# RC_Engine_Sound_ESP32_B.net
KiCad netlist of a schematic drawn in EAGLE
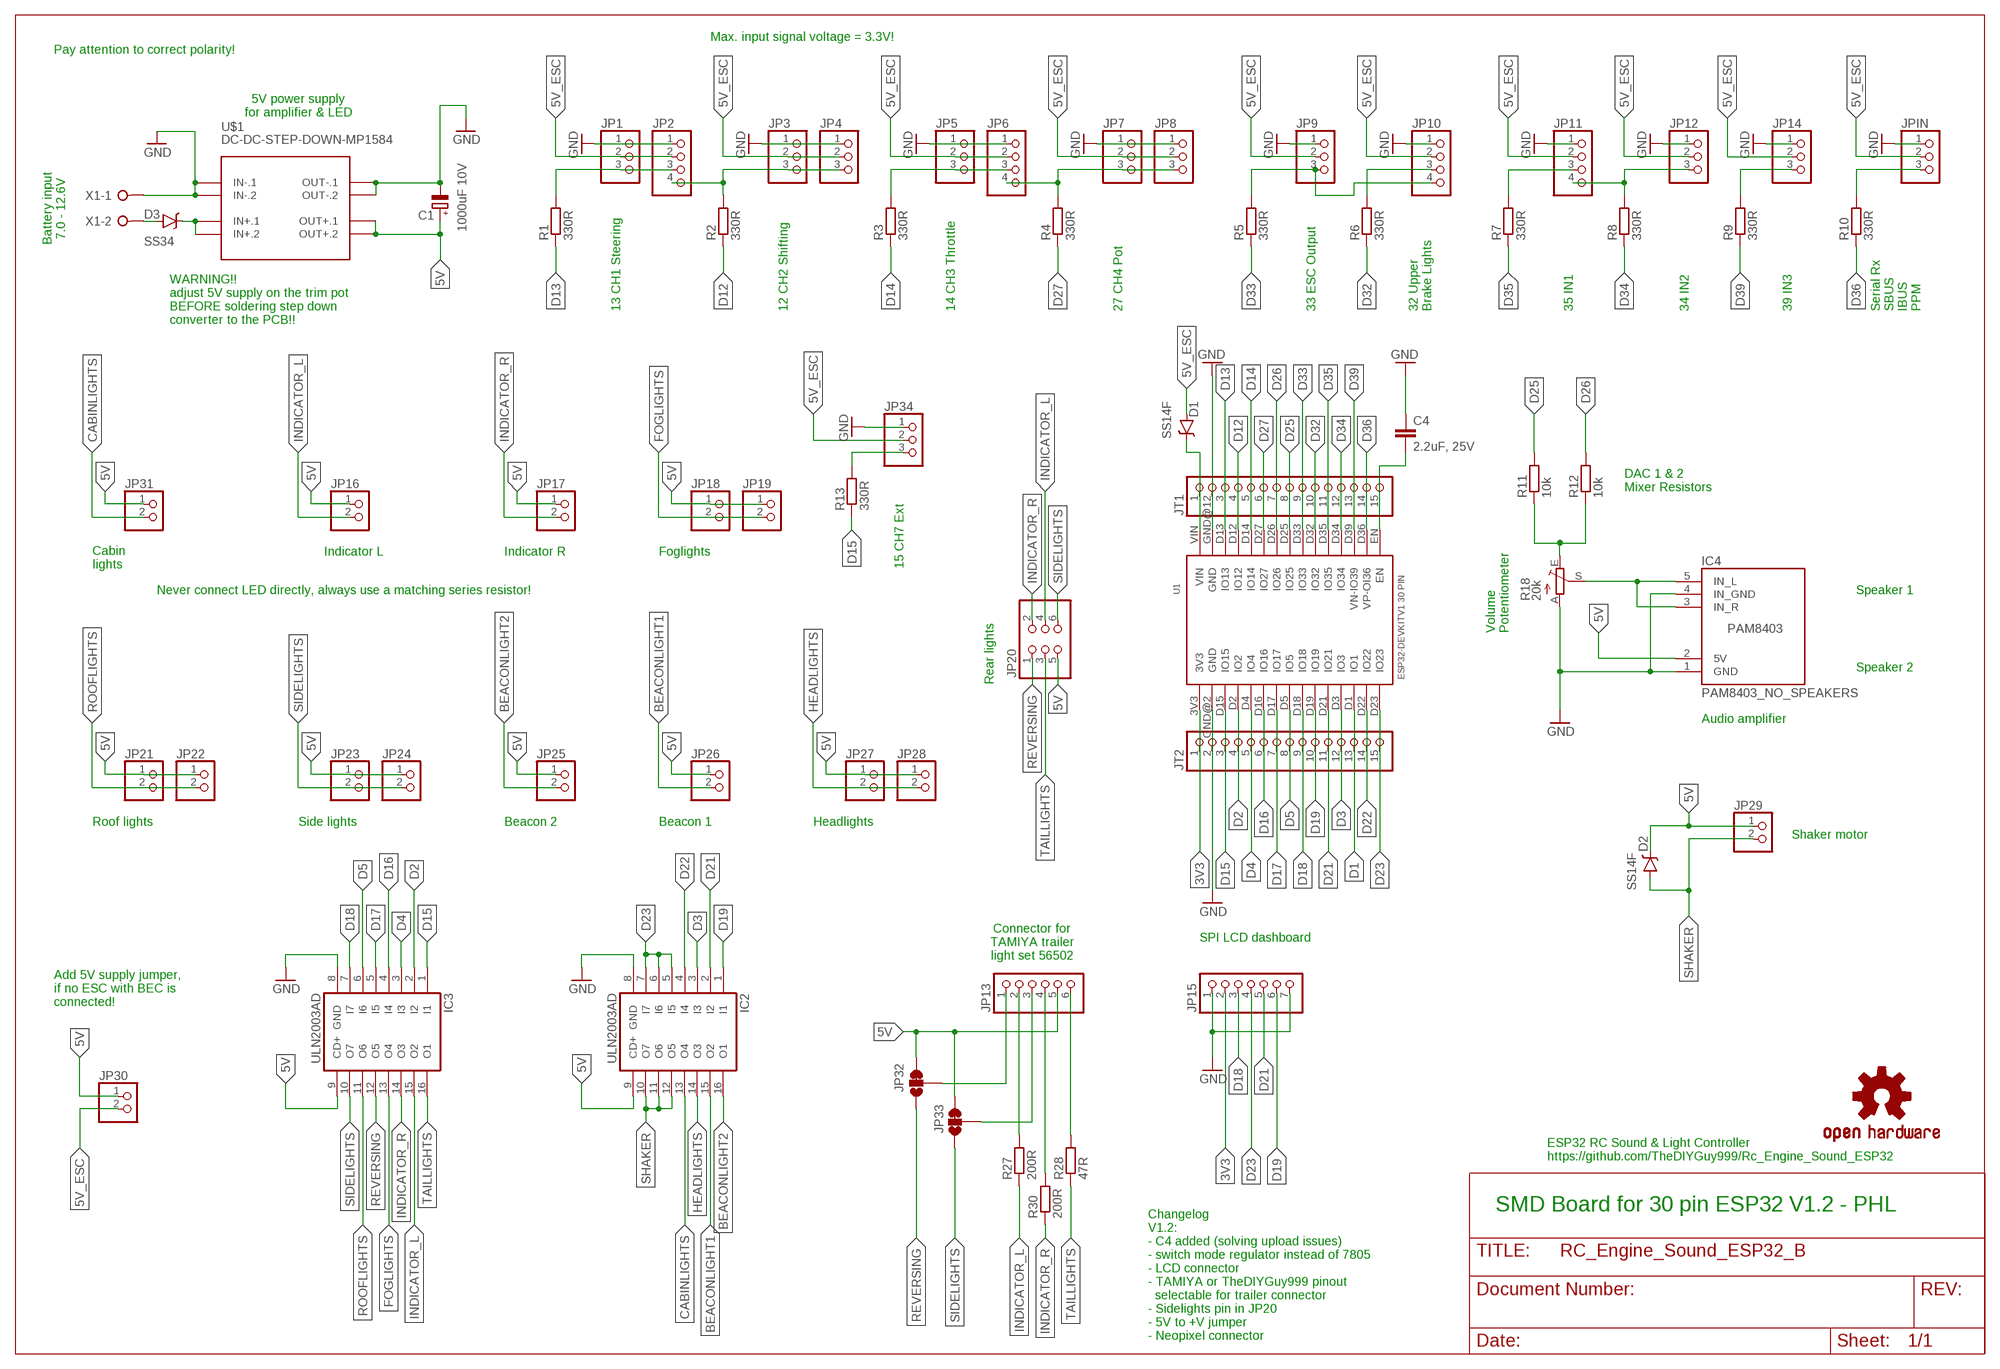
[diagram p0: schematic, sheet 1]

(export (version "E")
  (design (tool "Eeschema 10.0.6"))
  (components
    (comp (ref "C1")
      (value "1000uF 10V")
      (footprint "eagle-import:UD-10X10_NICHICON")
      (libsource (lib "eagle-import") (part "CPOL-EUUD-10X10"))
    )
    (comp (ref "C4")
      (value "2.2uF, 25V")
      (footprint "eagle-import:C1206")
      (libsource (lib "eagle-import") (part "C-EUC1206"))
    )
    (comp (ref "D1")
      (value "SS14F")
      (footprint "eagle-import:SMA-DIODE")
      (libsource (lib "eagle-import") (part "MBRA140"))
    )
    (comp (ref "D2")
      (value "SS14F")
      (footprint "eagle-import:SMA-DIODE")
      (libsource (lib "eagle-import") (part "MBRA140"))
    )
    (comp (ref "D3")
      (value "SS34")
      (footprint "eagle-import:SMA-DIODE")
      (libsource (lib "eagle-import") (part "MBRA140"))
    )
    (comp (ref "IC2")
      (value "ULN2003AD")
      (footprint "eagle-import:SO16")
      (libsource (lib "eagle-import") (part "ULN2003AD"))
    )
    (comp (ref "IC3")
      (value "ULN2003AD")
      (footprint "eagle-import:SO16")
      (libsource (lib "eagle-import") (part "ULN2003AD"))
    )
    (comp (ref "IC4")
      (value "PAM8403_NO_SPEAKERS")
      (footprint "eagle-import:PAM8403_NO_SPEAKERS")
      (libsource (lib "eagle-import") (part "PAM8403_NO_SPEAKERS"))
    )
    (comp (ref "JP1")
      (value "PINHD-1X3")
      (footprint "eagle-import:1X03")
      (libsource (lib "eagle-import") (part "PINHD-1X3"))
    )
    (comp (ref "JP2")
      (value "00_CUSTOM_PINHEAD_PINHD-1X4")
      (footprint "eagle-import:00_CUSTOM_PINHEAD_1X04")
      (libsource (lib "eagle-import") (part "00_CUSTOM_PINHEAD_PINHD-1X4"))
    )
    (comp (ref "JP3")
      (value "PINHD-1X3")
      (footprint "eagle-import:1X03")
      (libsource (lib "eagle-import") (part "PINHD-1X3"))
    )
    (comp (ref "JP4")
      (value "PINHD-1X3")
      (footprint "eagle-import:1X03")
      (libsource (lib "eagle-import") (part "PINHD-1X3"))
    )
    (comp (ref "JP5")
      (value "PINHD-1X3")
      (footprint "eagle-import:1X03")
      (libsource (lib "eagle-import") (part "PINHD-1X3"))
    )
    (comp (ref "JP6")
      (value "00_CUSTOM_PINHEAD_PINHD-1X4")
      (footprint "eagle-import:00_CUSTOM_PINHEAD_1X04")
      (libsource (lib "eagle-import") (part "00_CUSTOM_PINHEAD_PINHD-1X4"))
    )
    (comp (ref "JP7")
      (value "PINHD-1X3")
      (footprint "eagle-import:1X03")
      (libsource (lib "eagle-import") (part "PINHD-1X3"))
    )
    (comp (ref "JP8")
      (value "PINHD-1X3")
      (footprint "eagle-import:1X03")
      (libsource (lib "eagle-import") (part "PINHD-1X3"))
    )
    (comp (ref "JP9")
      (value "PINHD-1X3")
      (footprint "eagle-import:1X03")
      (libsource (lib "eagle-import") (part "PINHD-1X3"))
    )
    (comp (ref "JP10")
      (value "00_CUSTOM_PINHEAD_PINHD-1X4")
      (footprint "eagle-import:00_CUSTOM_PINHEAD_1X04")
      (libsource (lib "eagle-import") (part "00_CUSTOM_PINHEAD_PINHD-1X4"))
    )
    (comp (ref "JP11")
      (value "00_CUSTOM_PINHEAD_PINHD-1X4")
      (footprint "eagle-import:00_CUSTOM_PINHEAD_1X04")
      (libsource (lib "eagle-import") (part "00_CUSTOM_PINHEAD_PINHD-1X4"))
    )
    (comp (ref "JP12")
      (value "PINHD-1X3")
      (footprint "eagle-import:1X03")
      (libsource (lib "eagle-import") (part "PINHD-1X3"))
    )
    (comp (ref "JP13")
      (value "PINHD-1X6")
      (footprint "eagle-import:1X06")
      (libsource (lib "eagle-import") (part "PINHD-1X6"))
    )
    (comp (ref "JP14")
      (value "PINHD-1X3")
      (footprint "eagle-import:1X03")
      (libsource (lib "eagle-import") (part "PINHD-1X3"))
    )
    (comp (ref "JP15")
      (value "PINHD-1X7")
      (footprint "eagle-import:1X07")
      (libsource (lib "eagle-import") (part "PINHD-1X7"))
    )
    (comp (ref "JP16")
      (value "PINHD-1X2")
      (footprint "eagle-import:1X02")
      (libsource (lib "eagle-import") (part "PINHD-1X2"))
    )
    (comp (ref "JP17")
      (value "PINHD-1X2")
      (footprint "eagle-import:1X02")
      (libsource (lib "eagle-import") (part "PINHD-1X2"))
    )
    (comp (ref "JP18")
      (value "PINHD-1X2")
      (footprint "eagle-import:1X02")
      (libsource (lib "eagle-import") (part "PINHD-1X2"))
    )
    (comp (ref "JP19")
      (value "PINHD-1X2")
      (footprint "eagle-import:1X02")
      (libsource (lib "eagle-import") (part "PINHD-1X2"))
    )
    (comp (ref "JP20")
      (value "PINHD-2X3")
      (footprint "eagle-import:2X03")
      (libsource (lib "eagle-import") (part "PINHD-2X3"))
    )
    (comp (ref "JP21")
      (value "PINHD-1X2")
      (footprint "eagle-import:1X02")
      (libsource (lib "eagle-import") (part "PINHD-1X2"))
    )
    (comp (ref "JP22")
      (value "PINHD-1X2")
      (footprint "eagle-import:1X02")
      (libsource (lib "eagle-import") (part "PINHD-1X2"))
    )
    (comp (ref "JP23")
      (value "PINHD-1X2")
      (footprint "eagle-import:1X02")
      (libsource (lib "eagle-import") (part "PINHD-1X2"))
    )
    (comp (ref "JP24")
      (value "PINHD-1X2")
      (footprint "eagle-import:1X02")
      (libsource (lib "eagle-import") (part "PINHD-1X2"))
    )
    (comp (ref "JP25")
      (value "PINHD-1X2")
      (footprint "eagle-import:1X02")
      (libsource (lib "eagle-import") (part "PINHD-1X2"))
    )
    (comp (ref "JP26")
      (value "PINHD-1X2")
      (footprint "eagle-import:1X02")
      (libsource (lib "eagle-import") (part "PINHD-1X2"))
    )
    (comp (ref "JP27")
      (value "PINHD-1X2")
      (footprint "eagle-import:1X02")
      (libsource (lib "eagle-import") (part "PINHD-1X2"))
    )
    (comp (ref "JP28")
      (value "PINHD-1X2")
      (footprint "eagle-import:1X02")
      (libsource (lib "eagle-import") (part "PINHD-1X2"))
    )
    (comp (ref "JP29")
      (value "PINHD-1X2")
      (footprint "eagle-import:1X02")
      (libsource (lib "eagle-import") (part "PINHD-1X2"))
    )
    (comp (ref "JP30")
      (value "PINHD-1X2")
      (footprint "eagle-import:1X02")
      (libsource (lib "eagle-import") (part "PINHD-1X2"))
    )
    (comp (ref "JP31")
      (value "PINHD-1X2")
      (footprint "eagle-import:1X02")
      (libsource (lib "eagle-import") (part "PINHD-1X2"))
    )
    (comp (ref "JP32")
      (value "JUMPER-PAD-3-2OF3_NC_BY_TRACE_LARGE")
      (footprint "eagle-import:PAD-JUMPER-3-2OF3_NC_BY_TRACE_YES_SILK_LARGE")
      (libsource (lib "eagle-import") (part "JUMPER-PAD-3-2OF3_NC_BY_TRACE_LARGE"))
    )
    (comp (ref "JP33")
      (value "JUMPER-PAD-3-2OF3_NC_BY_TRACE_LARGE")
      (footprint "eagle-import:PAD-JUMPER-3-2OF3_NC_BY_TRACE_YES_SILK_LARGE")
      (libsource (lib "eagle-import") (part "JUMPER-PAD-3-2OF3_NC_BY_TRACE_LARGE"))
    )
    (comp (ref "JP34")
      (value "PINHD-1X3")
      (footprint "eagle-import:1X03")
      (libsource (lib "eagle-import") (part "PINHD-1X3"))
    )
    (comp (ref "JPIN")
      (value "PINHD-1X3")
      (footprint "eagle-import:1X03")
      (libsource (lib "eagle-import") (part "PINHD-1X3"))
    )
    (comp (ref "JT1")
      (value "00_CUSTOM_PINHEAD_PINHD-1X15")
      (footprint "eagle-import:00_CUSTOM_PINHEAD_1X15")
      (libsource (lib "eagle-import") (part "00_CUSTOM_PINHEAD_PINHD-1X15"))
    )
    (comp (ref "JT2")
      (value "00_CUSTOM_PINHEAD_PINHD-1X15")
      (footprint "eagle-import:00_CUSTOM_PINHEAD_1X15")
      (libsource (lib "eagle-import") (part "00_CUSTOM_PINHEAD_PINHD-1X15"))
    )
    (comp (ref "LOGO1")
      (value "OSHW-LOGOM")
      (footprint "eagle-import:OSHW-LOGO-M")
      (libsource (lib "eagle-import") (part "OSHW-LOGOM"))
    )
    (comp (ref "R1")
      (value "330R")
      (footprint "eagle-import:R0805")
      (libsource (lib "eagle-import") (part "R-EU_R0805"))
    )
    (comp (ref "R2")
      (value "330R")
      (footprint "eagle-import:R0805")
      (libsource (lib "eagle-import") (part "R-EU_R0805"))
    )
    (comp (ref "R3")
      (value "330R")
      (footprint "eagle-import:R0805")
      (libsource (lib "eagle-import") (part "R-EU_R0805"))
    )
    (comp (ref "R4")
      (value "330R")
      (footprint "eagle-import:R0805")
      (libsource (lib "eagle-import") (part "R-EU_R0805"))
    )
    (comp (ref "R5")
      (value "330R")
      (footprint "eagle-import:R0805")
      (libsource (lib "eagle-import") (part "R-EU_R0805"))
    )
    (comp (ref "R6")
      (value "330R")
      (footprint "eagle-import:R0805")
      (libsource (lib "eagle-import") (part "R-EU_R0805"))
    )
    (comp (ref "R7")
      (value "330R")
      (footprint "eagle-import:R0805")
      (libsource (lib "eagle-import") (part "R-EU_R0805"))
    )
    (comp (ref "R8")
      (value "330R")
      (footprint "eagle-import:R0805")
      (libsource (lib "eagle-import") (part "R-EU_R0805"))
    )
    (comp (ref "R9")
      (value "330R")
      (footprint "eagle-import:R0805")
      (libsource (lib "eagle-import") (part "R-EU_R0805"))
    )
    (comp (ref "R10")
      (value "330R")
      (footprint "eagle-import:R0805")
      (libsource (lib "eagle-import") (part "R-EU_R0805"))
    )
    (comp (ref "R11")
      (value "10k")
      (footprint "eagle-import:R0805")
      (libsource (lib "eagle-import") (part "R-EU_R0805"))
    )
    (comp (ref "R12")
      (value "10k")
      (footprint "eagle-import:R0805")
      (libsource (lib "eagle-import") (part "R-EU_R0805"))
    )
    (comp (ref "R13")
      (value "330R")
      (footprint "eagle-import:R0805")
      (libsource (lib "eagle-import") (part "R-EU_R0805"))
    )
    (comp (ref "R18")
      (value "20k")
      (footprint "eagle-import:S64W")
      (libsource (lib "eagle-import") (part "TRIM_EU-S64W"))
    )
    (comp (ref "R27")
      (value "200R")
      (footprint "eagle-import:R0805")
      (libsource (lib "eagle-import") (part "R-EU_R0805"))
    )
    (comp (ref "R28")
      (value "47R")
      (footprint "eagle-import:R0805")
      (libsource (lib "eagle-import") (part "R-EU_R0805"))
    )
    (comp (ref "R30")
      (value "200R")
      (footprint "eagle-import:R0805")
      (libsource (lib "eagle-import") (part "R-EU_R0805"))
    )
    (comp (ref "U$1")
      (value "DC-DC-STEP-DOWN-MP1584")
      (footprint "eagle-import:DC-DC-STEP-DOWN-MP1584")
      (libsource (lib "eagle-import") (part "DC-DC-STEP-DOWN-MP1584"))
    )
    (comp (ref "U1")
      (value "ESP32DEVKITV1")
      (footprint "eagle-import:ESP32-DEVKITV1")
      (libsource (lib "eagle-import") (part "ESP32DEVKITV1"))
    )
    (comp (ref "X1")
      (value "W237-02P")
      (footprint "eagle-import:W237-132")
      (libsource (lib "eagle-import") (part "W237-02P"))
    )
  )
  (nets
    (net (code "1") (name "3V3") (class "Default")
      (node (ref "JP15") (pin "2") (pinfunction "2_2") (pintype "passive"))
      (node (ref "JT2") (pin "1") (pinfunction "1_1") (pintype "passive"))
      (node (ref "U1") (pin "3V3") (pinfunction "3V3_3V3") (pintype "power_in"))
    )
    (net (code "2") (name "5V") (class "Default")
      (node (ref "C1") (pin "+") (pinfunction "+_+") (pintype "passive"))
      (node (ref "D2") (pin "C") (pinfunction "C_C") (pintype "passive"))
      (node (ref "IC2") (pin "9") (pinfunction "CD+_9") (pintype "passive"))
      (node (ref "IC3") (pin "9") (pinfunction "CD+_9") (pintype "passive"))
      (node (ref "IC4") (pin "2") (pinfunction "5V_2") (pintype "input"))
      (node (ref "JP13") (pin "5") (pinfunction "5_5") (pintype "passive"))
      (node (ref "JP16") (pin "1") (pinfunction "1_1") (pintype "passive"))
      (node (ref "JP17") (pin "1") (pinfunction "1_1") (pintype "passive"))
      (node (ref "JP18") (pin "1") (pinfunction "1_1") (pintype "passive"))
      (node (ref "JP19") (pin "1") (pinfunction "1_1") (pintype "passive"))
      (node (ref "JP20") (pin "5") (pinfunction "5_5") (pintype "passive"))
      (node (ref "JP21") (pin "1") (pinfunction "1_1") (pintype "passive"))
      (node (ref "JP22") (pin "1") (pinfunction "1_1") (pintype "passive"))
      (node (ref "JP23") (pin "1") (pinfunction "1_1") (pintype "passive"))
      (node (ref "JP24") (pin "1") (pinfunction "1_1") (pintype "passive"))
      (node (ref "JP25") (pin "1") (pinfunction "1_1") (pintype "passive"))
      (node (ref "JP26") (pin "1") (pinfunction "1_1") (pintype "passive"))
      (node (ref "JP27") (pin "1") (pinfunction "1_1") (pintype "passive"))
      (node (ref "JP28") (pin "1") (pinfunction "1_1") (pintype "passive"))
      (node (ref "JP29") (pin "1") (pinfunction "1_1") (pintype "passive"))
      (node (ref "JP30") (pin "1") (pinfunction "1_1") (pintype "passive"))
      (node (ref "JP31") (pin "1") (pinfunction "1_1") (pintype "passive"))
      (node (ref "JP32") (pin "3") (pinfunction "3_3") (pintype "passive"))
      (node (ref "JP33") (pin "3") (pinfunction "3_3") (pintype "passive"))
      (node (ref "U$1") (pin "OUT+.1") (pinfunction "OUT+.1_OUT+.1") (pintype "bidirectional"))
      (node (ref "U$1") (pin "OUT+.2") (pinfunction "OUT+.2_OUT+.2") (pintype "bidirectional"))
    )
    (net (code "3") (name "5V_ESC") (class "Default")
      (node (ref "D1") (pin "A") (pinfunction "A_A") (pintype "passive"))
      (node (ref "JP1") (pin "2") (pinfunction "2_2") (pintype "passive"))
      (node (ref "JP10") (pin "2") (pinfunction "2_2") (pintype "passive"))
      (node (ref "JP11") (pin "2") (pinfunction "2_2") (pintype "passive"))
      (node (ref "JP12") (pin "2") (pinfunction "2_2") (pintype "passive"))
      (node (ref "JP14") (pin "2") (pinfunction "2_2") (pintype "passive"))
      (node (ref "JP2") (pin "2") (pinfunction "2_2") (pintype "passive"))
      (node (ref "JP3") (pin "2") (pinfunction "2_2") (pintype "passive"))
      (node (ref "JP30") (pin "2") (pinfunction "2_2") (pintype "passive"))
      (node (ref "JP34") (pin "2") (pinfunction "2_2") (pintype "passive"))
      (node (ref "JP4") (pin "2") (pinfunction "2_2") (pintype "passive"))
      (node (ref "JP5") (pin "2") (pinfunction "2_2") (pintype "passive"))
      (node (ref "JP6") (pin "2") (pinfunction "2_2") (pintype "passive"))
      (node (ref "JP7") (pin "2") (pinfunction "2_2") (pintype "passive"))
      (node (ref "JP8") (pin "2") (pinfunction "2_2") (pintype "passive"))
      (node (ref "JP9") (pin "2") (pinfunction "2_2") (pintype "passive"))
      (node (ref "JPIN") (pin "2") (pinfunction "2_2") (pintype "passive"))
    )
    (net (code "4") (name "BEACONLIGHT1") (class "Default")
      (node (ref "IC2") (pin "15") (pinfunction "O2_15") (pintype "open_collector"))
      (node (ref "JP26") (pin "2") (pinfunction "2_2") (pintype "passive"))
    )
    (net (code "5") (name "BEACONLIGHT2") (class "Default")
      (node (ref "IC2") (pin "16") (pinfunction "O1_16") (pintype "open_collector"))
      (node (ref "JP25") (pin "2") (pinfunction "2_2") (pintype "passive"))
    )
    (net (code "6") (name "CABINLIGHTS") (class "Default")
      (node (ref "IC2") (pin "13") (pinfunction "O4_13") (pintype "open_collector"))
      (node (ref "JP31") (pin "2") (pinfunction "2_2") (pintype "passive"))
    )
    (net (code "7") (name "D1") (class "Default")
      (node (ref "JT2") (pin "13") (pinfunction "13_13") (pintype "passive"))
      (node (ref "U1") (pin "D1") (pinfunction "IO1_D1") (pintype "bidirectional"))
    )
    (net (code "8") (name "D2") (class "Default")
      (node (ref "IC3") (pin "2") (pinfunction "I2_2") (pintype "input"))
      (node (ref "JT2") (pin "4") (pinfunction "4_4") (pintype "passive"))
      (node (ref "U1") (pin "D2") (pinfunction "IO2_D2") (pintype "bidirectional"))
    )
    (net (code "9") (name "D3") (class "Default")
      (node (ref "IC2") (pin "3") (pinfunction "I3_3") (pintype "input"))
      (node (ref "JT2") (pin "12") (pinfunction "12_12") (pintype "passive"))
      (node (ref "U1") (pin "D3") (pinfunction "IO3_D3") (pintype "bidirectional"))
    )
    (net (code "10") (name "D4") (class "Default")
      (node (ref "IC3") (pin "3") (pinfunction "I3_3") (pintype "input"))
      (node (ref "JT2") (pin "5") (pinfunction "5_5") (pintype "passive"))
      (node (ref "U1") (pin "D4") (pinfunction "IO4_D4") (pintype "bidirectional"))
    )
    (net (code "11") (name "D5") (class "Default")
      (node (ref "IC3") (pin "6") (pinfunction "I6_6") (pintype "input"))
      (node (ref "JT2") (pin "8") (pinfunction "8_8") (pintype "passive"))
      (node (ref "U1") (pin "D5") (pinfunction "IO5_D5") (pintype "bidirectional"))
    )
    (net (code "12") (name "D12") (class "Default")
      (node (ref "JT1") (pin "4") (pinfunction "4_4") (pintype "passive"))
      (node (ref "R2") (pin "1") (pinfunction "1_1") (pintype "passive"))
      (node (ref "U1") (pin "D12") (pinfunction "IO12_D12") (pintype "bidirectional"))
    )
    (net (code "13") (name "D13") (class "Default")
      (node (ref "JT1") (pin "3") (pinfunction "3_3") (pintype "passive"))
      (node (ref "R1") (pin "1") (pinfunction "1_1") (pintype "passive"))
      (node (ref "U1") (pin "D13") (pinfunction "IO13_D13") (pintype "bidirectional"))
    )
    (net (code "14") (name "D14") (class "Default")
      (node (ref "JT1") (pin "5") (pinfunction "5_5") (pintype "passive"))
      (node (ref "R3") (pin "1") (pinfunction "1_1") (pintype "passive"))
      (node (ref "U1") (pin "D14") (pinfunction "IO14_D14") (pintype "bidirectional"))
    )
    (net (code "15") (name "D15") (class "Default")
      (node (ref "IC3") (pin "1") (pinfunction "I1_1") (pintype "input"))
      (node (ref "JT2") (pin "3") (pinfunction "3_3") (pintype "passive"))
      (node (ref "R13") (pin "1") (pinfunction "1_1") (pintype "passive"))
      (node (ref "U1") (pin "D15") (pinfunction "IO15_D15") (pintype "bidirectional"))
    )
    (net (code "16") (name "D16") (class "Default")
      (node (ref "IC3") (pin "4") (pinfunction "I4_4") (pintype "input"))
      (node (ref "JT2") (pin "6") (pinfunction "6_6") (pintype "passive"))
      (node (ref "U1") (pin "D16") (pinfunction "IO16_D16") (pintype "bidirectional"))
    )
    (net (code "17") (name "D17") (class "Default")
      (node (ref "IC3") (pin "5") (pinfunction "I5_5") (pintype "input"))
      (node (ref "JT2") (pin "7") (pinfunction "7_7") (pintype "passive"))
      (node (ref "U1") (pin "D17") (pinfunction "IO17_D17") (pintype "bidirectional"))
    )
    (net (code "18") (name "D18") (class "Default")
      (node (ref "IC3") (pin "7") (pinfunction "I7_7") (pintype "input"))
      (node (ref "JP15") (pin "3") (pinfunction "3_3") (pintype "passive"))
      (node (ref "JT2") (pin "9") (pinfunction "9_9") (pintype "passive"))
      (node (ref "U1") (pin "D18") (pinfunction "IO18_D18") (pintype "bidirectional"))
    )
    (net (code "19") (name "D19") (class "Default")
      (node (ref "IC2") (pin "1") (pinfunction "I1_1") (pintype "input"))
      (node (ref "JP15") (pin "6") (pinfunction "6_6") (pintype "passive"))
      (node (ref "JT2") (pin "10") (pinfunction "10_10") (pintype "passive"))
      (node (ref "U1") (pin "D19") (pinfunction "IO19_D19") (pintype "bidirectional"))
    )
    (net (code "20") (name "D21") (class "Default")
      (node (ref "IC2") (pin "2") (pinfunction "I2_2") (pintype "input"))
      (node (ref "JP15") (pin "5") (pinfunction "5_5") (pintype "passive"))
      (node (ref "JT2") (pin "11") (pinfunction "11_11") (pintype "passive"))
      (node (ref "U1") (pin "D21") (pinfunction "IO21_D21") (pintype "bidirectional"))
    )
    (net (code "21") (name "D22") (class "Default")
      (node (ref "IC2") (pin "4") (pinfunction "I4_4") (pintype "input"))
      (node (ref "JT2") (pin "14") (pinfunction "14_14") (pintype "passive"))
      (node (ref "U1") (pin "D22") (pinfunction "IO22_D22") (pintype "bidirectional"))
    )
    (net (code "22") (name "D23") (class "Default")
      (node (ref "IC2") (pin "5") (pinfunction "I5_5") (pintype "input"))
      (node (ref "IC2") (pin "6") (pinfunction "I6_6") (pintype "input"))
      (node (ref "IC2") (pin "7") (pinfunction "I7_7") (pintype "input"))
      (node (ref "JP15") (pin "4") (pinfunction "4_4") (pintype "passive"))
      (node (ref "JT2") (pin "15") (pinfunction "15_15") (pintype "passive"))
      (node (ref "U1") (pin "D23") (pinfunction "IO23_D23") (pintype "bidirectional"))
    )
    (net (code "23") (name "D25") (class "Default")
      (node (ref "JT1") (pin "8") (pinfunction "8_8") (pintype "passive"))
      (node (ref "R11") (pin "2") (pinfunction "2_2") (pintype "passive"))
      (node (ref "U1") (pin "D25") (pinfunction "IO25_D25") (pintype "bidirectional"))
    )
    (net (code "24") (name "D26") (class "Default")
      (node (ref "JT1") (pin "7") (pinfunction "7_7") (pintype "passive"))
      (node (ref "R12") (pin "2") (pinfunction "2_2") (pintype "passive"))
      (node (ref "U1") (pin "D26") (pinfunction "IO26_D26") (pintype "bidirectional"))
    )
    (net (code "25") (name "D27") (class "Default")
      (node (ref "JT1") (pin "6") (pinfunction "6_6") (pintype "passive"))
      (node (ref "R4") (pin "1") (pinfunction "1_1") (pintype "passive"))
      (node (ref "U1") (pin "D27") (pinfunction "IO27_D27") (pintype "bidirectional"))
    )
    (net (code "26") (name "D32") (class "Default")
      (node (ref "JT1") (pin "10") (pinfunction "10_10") (pintype "passive"))
      (node (ref "R6") (pin "1") (pinfunction "1_1") (pintype "passive"))
      (node (ref "U1") (pin "D32") (pinfunction "IO32_D32") (pintype "bidirectional"))
    )
    (net (code "27") (name "D33") (class "Default")
      (node (ref "JT1") (pin "9") (pinfunction "9_9") (pintype "passive"))
      (node (ref "R5") (pin "1") (pinfunction "1_1") (pintype "passive"))
      (node (ref "U1") (pin "D33") (pinfunction "IO33_D33") (pintype "bidirectional"))
    )
    (net (code "28") (name "D34") (class "Default")
      (node (ref "JT1") (pin "12") (pinfunction "12_12") (pintype "passive"))
      (node (ref "R8") (pin "1") (pinfunction "1_1") (pintype "passive"))
      (node (ref "U1") (pin "D34") (pinfunction "IO34_D34") (pintype "bidirectional"))
    )
    (net (code "29") (name "D35") (class "Default")
      (node (ref "JT1") (pin "11") (pinfunction "11_11") (pintype "passive"))
      (node (ref "R7") (pin "1") (pinfunction "1_1") (pintype "passive"))
      (node (ref "U1") (pin "D35") (pinfunction "IO35_D35") (pintype "bidirectional"))
    )
    (net (code "30") (name "D36") (class "Default")
      (node (ref "JT1") (pin "14") (pinfunction "14_14") (pintype "passive"))
      (node (ref "R10") (pin "1") (pinfunction "1_1") (pintype "passive"))
      (node (ref "U1") (pin "D36") (pinfunction "VP-OI36_D36") (pintype "bidirectional"))
    )
    (net (code "31") (name "D39") (class "Default")
      (node (ref "JT1") (pin "13") (pinfunction "13_13") (pintype "passive"))
      (node (ref "R9") (pin "1") (pinfunction "1_1") (pintype "passive"))
      (node (ref "U1") (pin "D39") (pinfunction "VN-IO39_D39") (pintype "bidirectional"))
    )
    (net (code "32") (name "FOGLIGHTS") (class "Default")
      (node (ref "IC3") (pin "13") (pinfunction "O4_13") (pintype "open_collector"))
      (node (ref "JP18") (pin "2") (pinfunction "2_2") (pintype "passive"))
      (node (ref "JP19") (pin "2") (pinfunction "2_2") (pintype "passive"))
    )
    (net (code "33") (name "GND") (class "Default")
      (node (ref "C1") (pin "-") (pinfunction "-_-") (pintype "passive"))
      (node (ref "C4") (pin "1") (pinfunction "1_1") (pintype "passive"))
      (node (ref "IC2") (pin "8") (pinfunction "GND_8") (pintype "power_in"))
      (node (ref "IC3") (pin "8") (pinfunction "GND_8") (pintype "power_in"))
      (node (ref "IC4") (pin "1") (pinfunction "GND_1") (pintype "input"))
      (node (ref "IC4") (pin "4") (pinfunction "IN_GND_4") (pintype "input"))
      (node (ref "JP1") (pin "1") (pinfunction "1_1") (pintype "passive"))
      (node (ref "JP10") (pin "1") (pinfunction "1_1") (pintype "passive"))
      (node (ref "JP11") (pin "1") (pinfunction "1_1") (pintype "passive"))
      (node (ref "JP12") (pin "1") (pinfunction "1_1") (pintype "passive"))
      (node (ref "JP14") (pin "1") (pinfunction "1_1") (pintype "passive"))
      (node (ref "JP15") (pin "1") (pinfunction "1_1") (pintype "passive"))
      (node (ref "JP15") (pin "7") (pinfunction "7_7") (pintype "passive"))
      (node (ref "JP2") (pin "1") (pinfunction "1_1") (pintype "passive"))
      (node (ref "JP3") (pin "1") (pinfunction "1_1") (pintype "passive"))
      (node (ref "JP34") (pin "1") (pinfunction "1_1") (pintype "passive"))
      (node (ref "JP4") (pin "1") (pinfunction "1_1") (pintype "passive"))
      (node (ref "JP5") (pin "1") (pinfunction "1_1") (pintype "passive"))
      (node (ref "JP6") (pin "1") (pinfunction "1_1") (pintype "passive"))
      (node (ref "JP7") (pin "1") (pinfunction "1_1") (pintype "passive"))
      (node (ref "JP8") (pin "1") (pinfunction "1_1") (pintype "passive"))
      (node (ref "JP9") (pin "1") (pinfunction "1_1") (pintype "passive"))
      (node (ref "JPIN") (pin "1") (pinfunction "1_1") (pintype "passive"))
      (node (ref "JT1") (pin "2") (pinfunction "2_2") (pintype "passive"))
      (node (ref "JT2") (pin "2") (pinfunction "2_2") (pintype "passive"))
      (node (ref "R18") (pin "A") (pinfunction "A_A") (pintype "passive"))
      (node (ref "U$1") (pin "IN-.1") (pinfunction "IN-.1_IN-.1") (pintype "bidirectional"))
      (node (ref "U$1") (pin "IN-.2") (pinfunction "IN-.2_IN-.2") (pintype "bidirectional"))
      (node (ref "U$1") (pin "OUT-.1") (pinfunction "OUT-.1_OUT-.1") (pintype "bidirectional"))
      (node (ref "U$1") (pin "OUT-.2") (pinfunction "OUT-.2_OUT-.2") (pintype "bidirectional"))
      (node (ref "U1") (pin "GND@1") (pinfunction "GND_GND@1") (pintype "power_in"))
      (node (ref "U1") (pin "GND@2") (pinfunction "GND_GND@2") (pintype "power_in"))
      (node (ref "X1") (pin "1") (pinfunction "KL_1") (pintype "passive"))
    )
    (net (code "34") (name "HEADLIGHTS") (class "Default")
      (node (ref "IC2") (pin "14") (pinfunction "O3_14") (pintype "open_collector"))
      (node (ref "JP27") (pin "2") (pinfunction "2_2") (pintype "passive"))
      (node (ref "JP28") (pin "2") (pinfunction "2_2") (pintype "passive"))
    )
    (net (code "35") (name "INDICATOR_L") (class "Default")
      (node (ref "IC3") (pin "15") (pinfunction "O2_15") (pintype "open_collector"))
      (node (ref "JP16") (pin "2") (pinfunction "2_2") (pintype "passive"))
      (node (ref "JP20") (pin "4") (pinfunction "4_4") (pintype "passive"))
      (node (ref "R27") (pin "1") (pinfunction "1_1") (pintype "passive"))
    )
    (net (code "36") (name "INDICATOR_R") (class "Default")
      (node (ref "IC3") (pin "14") (pinfunction "O3_14") (pintype "open_collector"))
      (node (ref "JP17") (pin "2") (pinfunction "2_2") (pintype "passive"))
      (node (ref "JP20") (pin "2") (pinfunction "2_2") (pintype "passive"))
      (node (ref "R30") (pin "1") (pinfunction "1_1") (pintype "passive"))
    )
    (net (code "37") (name "Net-(C4-Pad2)") (class "Default")
      (node (ref "C4") (pin "2") (pinfunction "2_2") (pintype "passive"))
      (node (ref "JT1") (pin "15") (pinfunction "15_15") (pintype "passive"))
      (node (ref "U1") (pin "EN") (pinfunction "EN_EN") (pintype "bidirectional"))
    )
    (net (code "38") (name "Net-(D1-PadC)") (class "Default")
      (node (ref "D1") (pin "C") (pinfunction "C_C") (pintype "passive"))
      (node (ref "JT1") (pin "1") (pinfunction "1_1") (pintype "passive"))
      (node (ref "U1") (pin "VIN") (pinfunction "VIN_VIN") (pintype "power_in"))
    )
    (net (code "39") (name "Net-(D3-PadC)") (class "Default")
      (node (ref "D3") (pin "C") (pinfunction "C_C") (pintype "passive"))
      (node (ref "U$1") (pin "IN+.1") (pinfunction "IN+.1_IN+.1") (pintype "bidirectional"))
      (node (ref "U$1") (pin "IN+.2") (pinfunction "IN+.2_IN+.2") (pintype "bidirectional"))
    )
    (net (code "40") (name "Net-(IC4-IN_L)") (class "Default")
      (node (ref "IC4") (pin "3") (pinfunction "IN_R_3") (pintype "input"))
      (node (ref "IC4") (pin "5") (pinfunction "IN_L_5") (pintype "input"))
      (node (ref "R18") (pin "S") (pinfunction "S_S") (pintype "passive"))
    )
    (net (code "41") (name "Net-(JP1-Pad3)") (class "Default")
      (node (ref "JP1") (pin "3") (pinfunction "3_3") (pintype "passive"))
      (node (ref "JP2") (pin "3") (pinfunction "3_3") (pintype "passive"))
      (node (ref "R1") (pin "2") (pinfunction "2_2") (pintype "passive"))
    )
    (net (code "42") (name "Net-(JP2-Pad4)") (class "Default")
      (node (ref "JP2") (pin "4") (pinfunction "4_4") (pintype "passive"))
      (node (ref "JP3") (pin "3") (pinfunction "3_3") (pintype "passive"))
      (node (ref "JP4") (pin "3") (pinfunction "3_3") (pintype "passive"))
      (node (ref "R2") (pin "2") (pinfunction "2_2") (pintype "passive"))
    )
    (net (code "43") (name "Net-(JP5-Pad3)") (class "Default")
      (node (ref "JP5") (pin "3") (pinfunction "3_3") (pintype "passive"))
      (node (ref "JP6") (pin "3") (pinfunction "3_3") (pintype "passive"))
      (node (ref "R3") (pin "2") (pinfunction "2_2") (pintype "passive"))
    )
    (net (code "44") (name "Net-(JP6-Pad4)") (class "Default")
      (node (ref "JP6") (pin "4") (pinfunction "4_4") (pintype "passive"))
      (node (ref "JP7") (pin "3") (pinfunction "3_3") (pintype "passive"))
      (node (ref "JP8") (pin "3") (pinfunction "3_3") (pintype "passive"))
      (node (ref "R4") (pin "2") (pinfunction "2_2") (pintype "passive"))
    )
    (net (code "45") (name "Net-(JP10-Pad3)") (class "Default")
      (node (ref "JP10") (pin "3") (pinfunction "3_3") (pintype "passive"))
      (node (ref "R6") (pin "2") (pinfunction "2_2") (pintype "passive"))
    )
    (net (code "46") (name "Net-(JP10-Pad4)") (class "Default")
      (node (ref "JP10") (pin "4") (pinfunction "4_4") (pintype "passive"))
      (node (ref "JP9") (pin "3") (pinfunction "3_3") (pintype "passive"))
      (node (ref "R5") (pin "2") (pinfunction "2_2") (pintype "passive"))
    )
    (net (code "47") (name "Net-(JP11-Pad3)") (class "Default")
      (node (ref "JP11") (pin "3") (pinfunction "3_3") (pintype "passive"))
      (node (ref "R7") (pin "2") (pinfunction "2_2") (pintype "passive"))
    )
    (net (code "48") (name "Net-(JP11-Pad4)") (class "Default")
      (node (ref "JP11") (pin "4") (pinfunction "4_4") (pintype "passive"))
      (node (ref "JP12") (pin "3") (pinfunction "3_3") (pintype "passive"))
      (node (ref "R8") (pin "2") (pinfunction "2_2") (pintype "passive"))
    )
    (net (code "49") (name "Net-(JP13-Pad1)") (class "Default")
      (node (ref "JP13") (pin "1") (pinfunction "1_1") (pintype "passive"))
      (node (ref "JP32") (pin "2") (pinfunction "2_2") (pintype "passive"))
    )
    (net (code "50") (name "Net-(JP13-Pad2)") (class "Default")
      (node (ref "JP13") (pin "2") (pinfunction "2_2") (pintype "passive"))
      (node (ref "R27") (pin "2") (pinfunction "2_2") (pintype "passive"))
    )
    (net (code "51") (name "Net-(JP13-Pad3)") (class "Default")
      (node (ref "JP13") (pin "3") (pinfunction "3_3") (pintype "passive"))
      (node (ref "JP33") (pin "2") (pinfunction "2_2") (pintype "passive"))
    )
    (net (code "52") (name "Net-(JP13-Pad4)") (class "Default")
      (node (ref "JP13") (pin "4") (pinfunction "4_4") (pintype "passive"))
      (node (ref "R30") (pin "2") (pinfunction "2_2") (pintype "passive"))
    )
    (net (code "53") (name "Net-(JP13-Pad6)") (class "Default")
      (node (ref "JP13") (pin "6") (pinfunction "6_6") (pintype "passive"))
      (node (ref "R28") (pin "2") (pinfunction "2_2") (pintype "passive"))
    )
    (net (code "54") (name "Net-(JP14-Pad3)") (class "Default")
      (node (ref "JP14") (pin "3") (pinfunction "3_3") (pintype "passive"))
      (node (ref "R9") (pin "2") (pinfunction "2_2") (pintype "passive"))
    )
    (net (code "55") (name "Net-(JP34-Pad3)") (class "Default")
      (node (ref "JP34") (pin "3") (pinfunction "3_3") (pintype "passive"))
      (node (ref "R13") (pin "2") (pinfunction "2_2") (pintype "passive"))
    )
    (net (code "56") (name "Net-(JPIN-Pad3)") (class "Default")
      (node (ref "JPIN") (pin "3") (pinfunction "3_3") (pintype "passive"))
      (node (ref "R10") (pin "2") (pinfunction "2_2") (pintype "passive"))
    )
    (net (code "57") (name "Net-(R11-Pad1)") (class "Default")
      (node (ref "R11") (pin "1") (pinfunction "1_1") (pintype "passive"))
      (node (ref "R12") (pin "1") (pinfunction "1_1") (pintype "passive"))
      (node (ref "R18") (pin "E") (pinfunction "E_E") (pintype "passive"))
    )
    (net (code "58") (name "Net-(X1B-KL)") (class "Default")
      (node (ref "D3") (pin "A") (pinfunction "A_A") (pintype "passive"))
      (node (ref "X1") (pin "2") (pinfunction "KL_2") (pintype "passive"))
    )
    (net (code "59") (name "REVERSING") (class "Default")
      (node (ref "IC3") (pin "12") (pinfunction "O5_12") (pintype "open_collector"))
      (node (ref "JP20") (pin "1") (pinfunction "1_1") (pintype "passive"))
      (node (ref "JP32") (pin "1") (pinfunction "1_1") (pintype "passive"))
    )
    (net (code "60") (name "ROOFLIGHTS") (class "Default")
      (node (ref "IC3") (pin "11") (pinfunction "O6_11") (pintype "open_collector"))
      (node (ref "JP21") (pin "2") (pinfunction "2_2") (pintype "passive"))
      (node (ref "JP22") (pin "2") (pinfunction "2_2") (pintype "passive"))
    )
    (net (code "61") (name "SHAKER") (class "Default")
      (node (ref "D2") (pin "A") (pinfunction "A_A") (pintype "passive"))
      (node (ref "IC2") (pin "10") (pinfunction "O7_10") (pintype "open_collector"))
      (node (ref "IC2") (pin "11") (pinfunction "O6_11") (pintype "open_collector"))
      (node (ref "IC2") (pin "12") (pinfunction "O5_12") (pintype "open_collector"))
      (node (ref "JP29") (pin "2") (pinfunction "2_2") (pintype "passive"))
    )
    (net (code "62") (name "SIDELIGHTS") (class "Default")
      (node (ref "IC3") (pin "10") (pinfunction "O7_10") (pintype "open_collector"))
      (node (ref "JP20") (pin "6") (pinfunction "6_6") (pintype "passive"))
      (node (ref "JP23") (pin "2") (pinfunction "2_2") (pintype "passive"))
      (node (ref "JP24") (pin "2") (pinfunction "2_2") (pintype "passive"))
      (node (ref "JP33") (pin "1") (pinfunction "1_1") (pintype "passive"))
    )
    (net (code "63") (name "TAILLIGHTS") (class "Default")
      (node (ref "IC3") (pin "16") (pinfunction "O1_16") (pintype "open_collector"))
      (node (ref "JP20") (pin "3") (pinfunction "3_3") (pintype "passive"))
      (node (ref "R28") (pin "1") (pinfunction "1_1") (pintype "passive"))
    )
  )
)
